# FPGA.net
KiCad netlist of a schematic drawn in Altium Designer
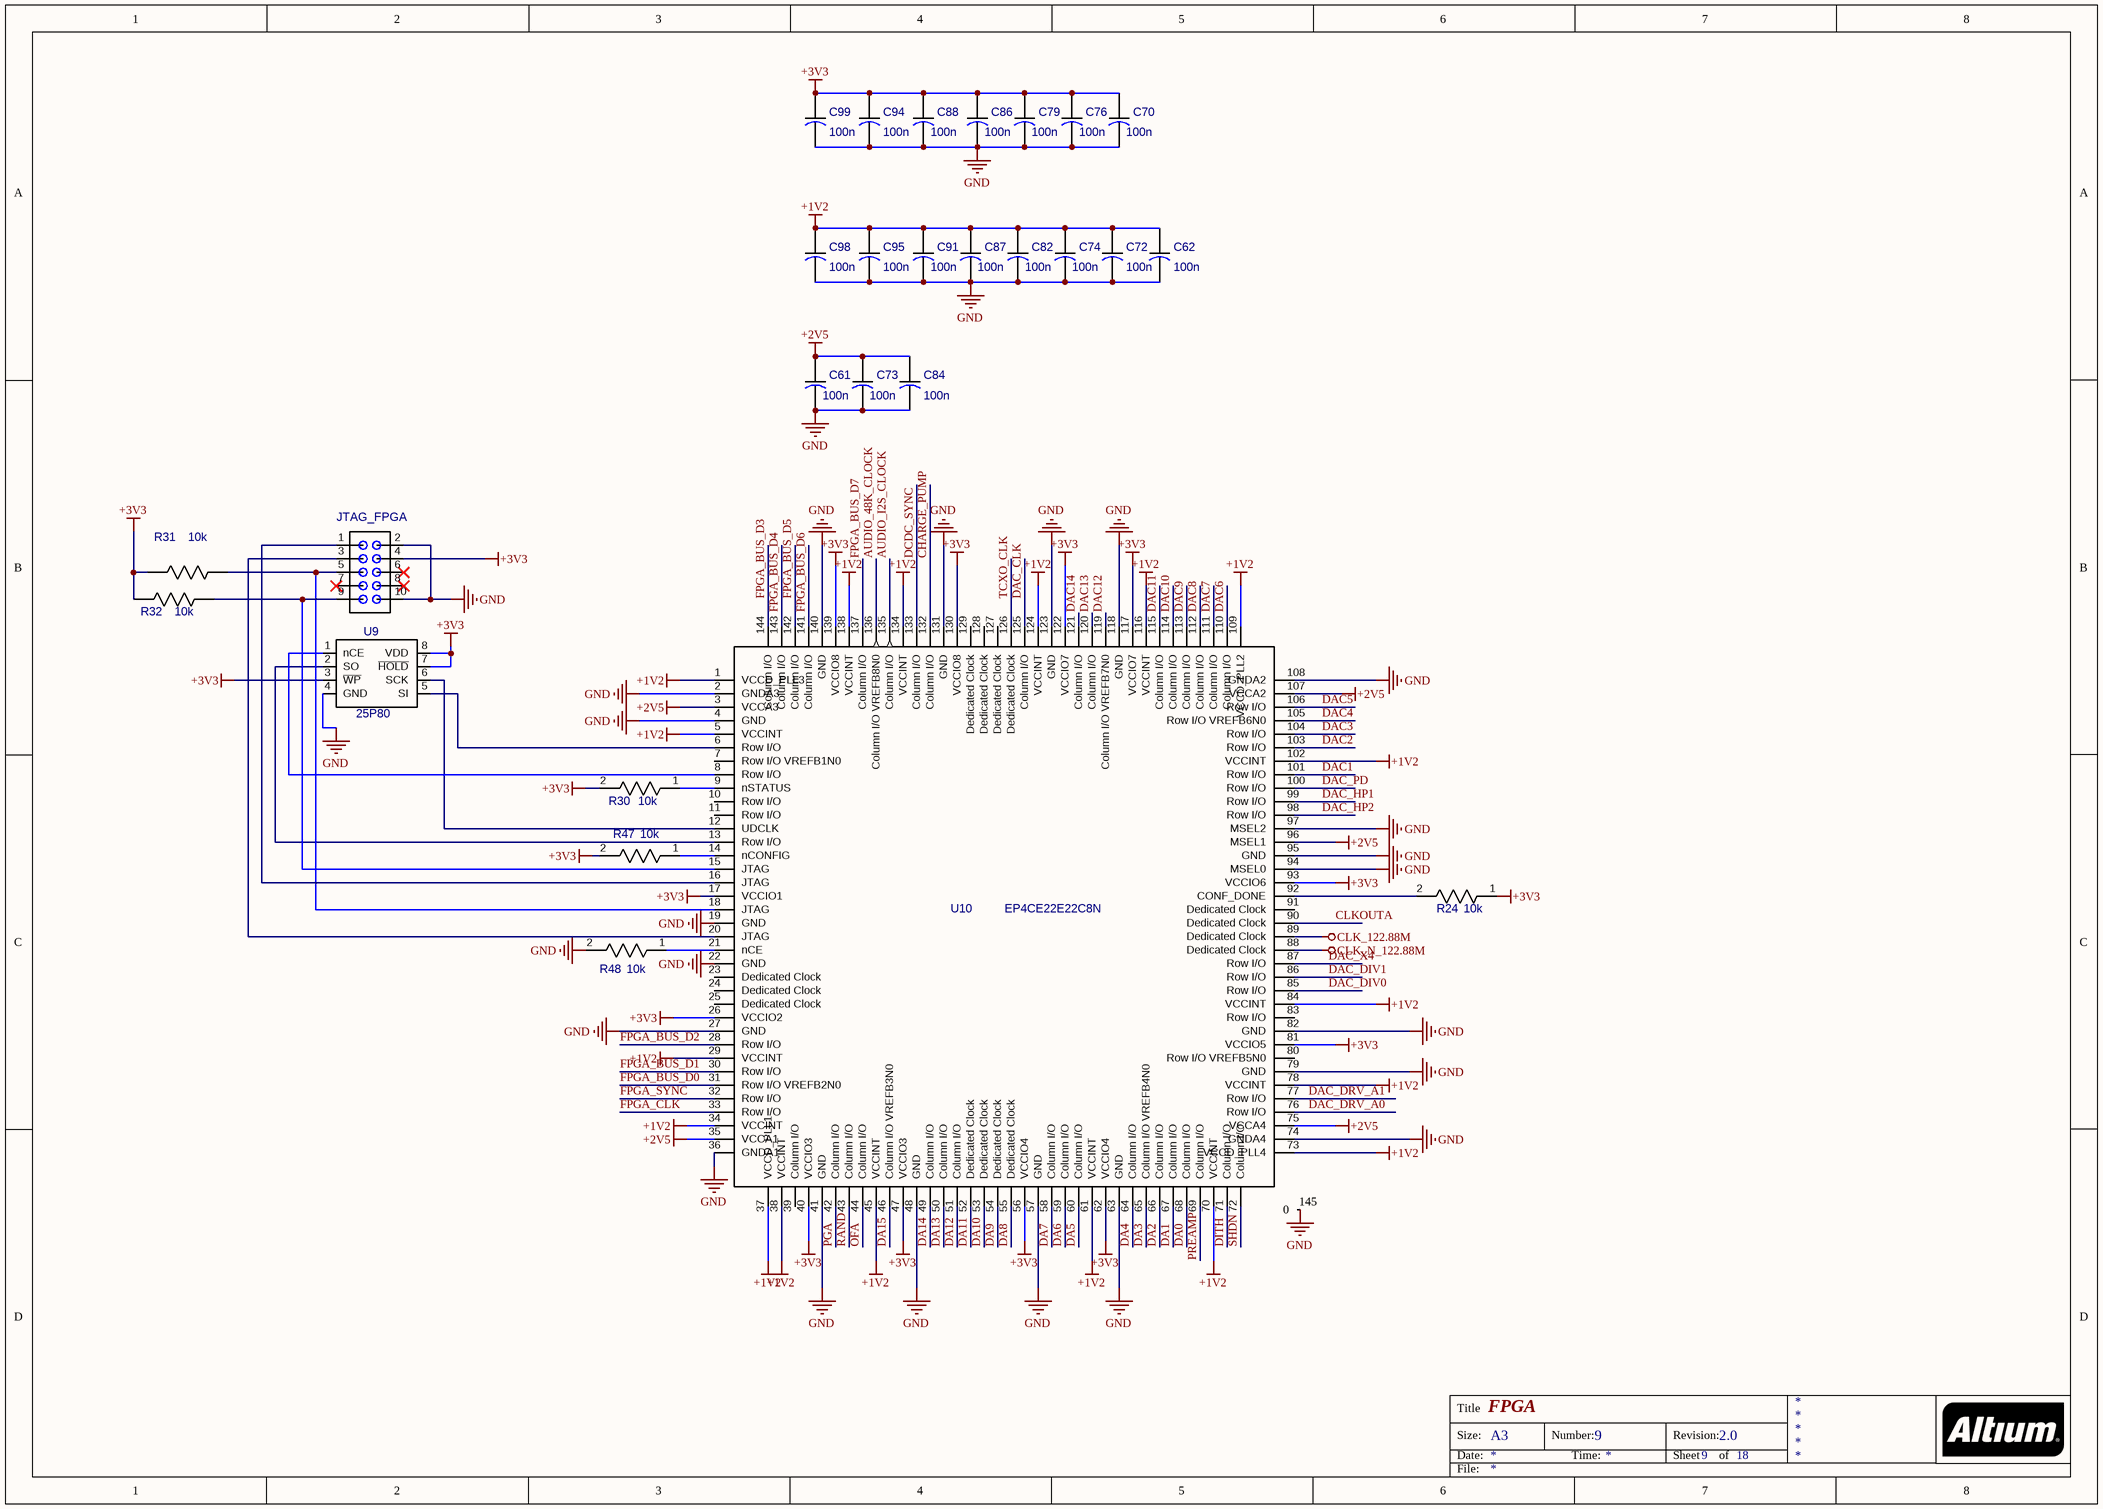
[diagram p0: FPGA.SchDoc]

(export (version "E")
  (design (tool "Eeschema 10.0.6"))
  (components
    (comp (ref "C61")
      (value "100n")
      (footprint "CAP_0805")
      (description "CAP_0805")
      (libsource (lib "*") (part "CAP_0805"))
    )
    (comp (ref "C62")
      (value "100n")
      (footprint "CAP_0805")
      (description "CAP_0805")
      (libsource (lib "*") (part "CAP_0805"))
    )
    (comp (ref "C70")
      (value "100n")
      (footprint "CAP_0805")
      (description "CAP_0805")
      (libsource (lib "*") (part "CAP_0805"))
    )
    (comp (ref "C72")
      (value "100n")
      (footprint "CAP_0805")
      (description "CAP_0805")
      (libsource (lib "*") (part "CAP_0805"))
    )
    (comp (ref "C73")
      (value "100n")
      (footprint "CAP_0805")
      (description "CAP_0805")
      (libsource (lib "*") (part "CAP_0805"))
    )
    (comp (ref "C74")
      (value "100n")
      (footprint "CAP_0805")
      (description "CAP_0805")
      (libsource (lib "*") (part "CAP_0805"))
    )
    (comp (ref "C76")
      (value "100n")
      (footprint "CAP_0805")
      (description "CAP_0805")
      (libsource (lib "*") (part "CAP_0805"))
    )
    (comp (ref "C79")
      (value "100n")
      (footprint "CAP_0805")
      (description "CAP_0805")
      (libsource (lib "*") (part "CAP_0805"))
    )
    (comp (ref "C82")
      (value "100n")
      (footprint "CAP_0805")
      (description "CAP_0805")
      (libsource (lib "*") (part "CAP_0805"))
    )
    (comp (ref "C84")
      (value "100n")
      (footprint "CAP_0805")
      (description "CAP_0805")
      (libsource (lib "*") (part "CAP_0805"))
    )
    (comp (ref "C86")
      (value "100n")
      (footprint "CAP_0805")
      (description "CAP_0805")
      (libsource (lib "*") (part "CAP_0805"))
    )
    (comp (ref "C87")
      (value "100n")
      (footprint "CAP_0805")
      (description "CAP_0805")
      (libsource (lib "*") (part "CAP_0805"))
    )
    (comp (ref "C88")
      (value "100n")
      (footprint "CAP_0805")
      (description "CAP_0805")
      (libsource (lib "*") (part "CAP_0805"))
    )
    (comp (ref "C91")
      (value "100n")
      (footprint "CAP_0805")
      (description "CAP_0805")
      (libsource (lib "*") (part "CAP_0805"))
    )
    (comp (ref "C94")
      (value "100n")
      (footprint "CAP_0805")
      (description "CAP_0805")
      (libsource (lib "*") (part "CAP_0805"))
    )
    (comp (ref "C95")
      (value "100n")
      (footprint "CAP_0805")
      (description "CAP_0805")
      (libsource (lib "*") (part "CAP_0805"))
    )
    (comp (ref "C98")
      (value "100n")
      (footprint "CAP_0805")
      (description "CAP_0805")
      (libsource (lib "*") (part "CAP_0805"))
    )
    (comp (ref "C99")
      (value "100n")
      (footprint "CAP_0805")
      (description "CAP_0805")
      (libsource (lib "*") (part "CAP_0805"))
    )
    (comp (ref "JTAG_FPGA")
      (value "~")
      (footprint "IDC10")
      (description "2*5 Pin")
      (libsource (lib "*") (part "IDC10"))
    )
    (comp (ref "R24")
      (value "10k")
      (footprint "RES_0805")
      (description "RES_0805")
      (libsource (lib "*") (part "RES_0805"))
    )
    (comp (ref "R30")
      (value "10k")
      (footprint "RES_0805")
      (description "RES_0805")
      (libsource (lib "*") (part "RES_0805"))
    )
    (comp (ref "R31")
      (value "10k")
      (footprint "RES_0805")
      (description "RES_0805")
      (libsource (lib "") (part "RES_0805_1"))
    )
    (comp (ref "R32")
      (value "10k")
      (footprint "RES_0805")
      (description "RES_0805")
      (libsource (lib "") (part "RES_0805_1"))
    )
    (comp (ref "R47")
      (value "10k")
      (footprint "RES_0805")
      (description "RES_0805")
      (libsource (lib "*") (part "RES_0805"))
    )
    (comp (ref "R48")
      (value "10k")
      (footprint "RES_0805")
      (description "RES_0805")
      (libsource (lib "*") (part "RES_0805"))
    )
    (comp (ref "U9") (value "25P80") (footprint "25P80") (libsource (lib "*") (part "25P80")))
    (comp (ref "U10")
      (value "EP4CE22E22C8N")
      (footprint "QFP144-20-2222A")
      (libsource (lib "*") (part "EP4CE22E22C8N"))
    )
  )
  (nets
    (net (code "1") (name "+1V2") (class "Default")
      (node (ref "C62") (pin "1") (pinfunction "1_1") (pintype "passive"))
      (node (ref "C72") (pin "1") (pinfunction "1_1") (pintype "passive"))
      (node (ref "C74") (pin "1") (pinfunction "1_1") (pintype "passive"))
      (node (ref "C82") (pin "1") (pinfunction "1_1") (pintype "passive"))
      (node (ref "C87") (pin "1") (pinfunction "1_1") (pintype "passive"))
      (node (ref "C91") (pin "1") (pinfunction "1_1") (pintype "passive"))
      (node (ref "C95") (pin "1") (pinfunction "1_1") (pintype "passive"))
      (node (ref "C98") (pin "1") (pinfunction "1_1") (pintype "passive"))
      (node (ref "U10") (pin "1") (pinfunction "VCCD_PLL3_1") (pintype "passive"))
      (node (ref "U10") (pin "102") (pinfunction "VCCINT_102") (pintype "passive"))
      (node (ref "U10") (pin "109") (pinfunction "VCCD_PLL2_109") (pintype "passive"))
      (node (ref "U10") (pin "116") (pinfunction "VCCINT_116") (pintype "passive"))
      (node (ref "U10") (pin "124") (pinfunction "VCCINT_124") (pintype "passive"))
      (node (ref "U10") (pin "134") (pinfunction "VCCINT_134") (pintype "passive"))
      (node (ref "U10") (pin "138") (pinfunction "VCCINT_138") (pintype "passive"))
      (node (ref "U10") (pin "29") (pinfunction "VCCINT_29") (pintype "passive"))
      (node (ref "U10") (pin "34") (pinfunction "VCCINT_34") (pintype "passive"))
      (node (ref "U10") (pin "37") (pinfunction "VCCD_PLL1_37") (pintype "passive"))
      (node (ref "U10") (pin "38") (pinfunction "VCCINT_38") (pintype "passive"))
      (node (ref "U10") (pin "45") (pinfunction "VCCINT_45") (pintype "passive"))
      (node (ref "U10") (pin "5") (pinfunction "VCCINT_5") (pintype "passive"))
      (node (ref "U10") (pin "61") (pinfunction "VCCINT_61") (pintype "passive"))
      (node (ref "U10") (pin "70") (pinfunction "VCCINT_70") (pintype "passive"))
      (node (ref "U10") (pin "73") (pinfunction "VCCD_PLL4_73") (pintype "passive"))
      (node (ref "U10") (pin "78") (pinfunction "VCCINT_78") (pintype "passive"))
      (node (ref "U10") (pin "84") (pinfunction "VCCINT_84") (pintype "passive"))
    )
    (net (code "2") (name "+2V5") (class "Default")
      (node (ref "C61") (pin "1") (pinfunction "1_1") (pintype "passive"))
      (node (ref "C73") (pin "1") (pinfunction "1_1") (pintype "passive"))
      (node (ref "C84") (pin "1") (pinfunction "1_1") (pintype "passive"))
      (node (ref "U10") (pin "107") (pinfunction "VCCA2_107") (pintype "passive"))
      (node (ref "U10") (pin "3") (pinfunction "VCCA3_3") (pintype "passive"))
      (node (ref "U10") (pin "35") (pinfunction "VCCA1_35") (pintype "passive"))
      (node (ref "U10") (pin "75") (pinfunction "VCCA4_75") (pintype "passive"))
      (node (ref "U10") (pin "96") (pinfunction "MSEL1_96") (pintype "passive"))
    )
    (net (code "3") (name "+3V3") (class "Default")
      (node (ref "C70") (pin "1") (pinfunction "1_1") (pintype "passive"))
      (node (ref "C76") (pin "1") (pinfunction "1_1") (pintype "passive"))
      (node (ref "C79") (pin "1") (pinfunction "1_1") (pintype "passive"))
      (node (ref "C86") (pin "1") (pinfunction "1_1") (pintype "passive"))
      (node (ref "C88") (pin "1") (pinfunction "1_1") (pintype "passive"))
      (node (ref "C94") (pin "1") (pinfunction "1_1") (pintype "passive"))
      (node (ref "C99") (pin "1") (pinfunction "1_1") (pintype "passive"))
      (node (ref "JTAG_FPGA") (pin "4") (pinfunction "4_4") (pintype "passive"))
      (node (ref "R24") (pin "1") (pinfunction "1_1") (pintype "passive"))
      (node (ref "R30") (pin "2") (pinfunction "2_2") (pintype "passive"))
      (node (ref "R31") (pin "2") (pinfunction "2_2") (pintype "passive"))
      (node (ref "R32") (pin "2") (pinfunction "2_2") (pintype "passive"))
      (node (ref "R47") (pin "2") (pinfunction "2_2") (pintype "passive"))
      (node (ref "U10") (pin "117") (pinfunction "VCCIO7_117") (pintype "passive"))
      (node (ref "U10") (pin "122") (pinfunction "VCCIO7_122") (pintype "passive"))
      (node (ref "U10") (pin "130") (pinfunction "VCCIO8_130") (pintype "passive"))
      (node (ref "U10") (pin "139") (pinfunction "VCCIO8_139") (pintype "passive"))
      (node (ref "U10") (pin "17") (pinfunction "VCCIO1_17") (pintype "passive"))
      (node (ref "U10") (pin "26") (pinfunction "VCCIO2_26") (pintype "passive"))
      (node (ref "U10") (pin "40") (pinfunction "VCCIO3_40") (pintype "passive"))
      (node (ref "U10") (pin "47") (pinfunction "VCCIO3_47") (pintype "passive"))
      (node (ref "U10") (pin "56") (pinfunction "VCCIO4_56") (pintype "passive"))
      (node (ref "U10") (pin "62") (pinfunction "VCCIO4_62") (pintype "passive"))
      (node (ref "U10") (pin "81") (pinfunction "VCCIO5_81") (pintype "passive"))
      (node (ref "U10") (pin "93") (pinfunction "VCCIO6_93") (pintype "passive"))
      (node (ref "U9") (pin "3") (pinfunction "~{WP}_3") (pintype "passive"))
      (node (ref "U9") (pin "7") (pinfunction "~{HOLD}_7") (pintype "passive"))
      (node (ref "U9") (pin "8") (pinfunction "VDD_8") (pintype "passive"))
    )
    (net (code "4") (name "/AUDIO_48K_CLOCK") (class "Default")
      (node (ref "U10") (pin "136") (pinfunction "Column_I/O_VREFB8N0_136") (pintype "output"))
    )
    (net (code "5") (name "/AUDIO_I2S_CLOCK") (class "Default")
      (node (ref "U10") (pin "135") (pinfunction "Column_I/O_135") (pintype "output"))
    )
    (net (code "6") (name "/CHARGE_PUMP") (class "Default")
      (node (ref "U10") (pin "132") (pinfunction "Column_I/O_132") (pintype "passive"))
    )
    (net (code "7") (name "/CLKOUTA") (class "Default")
      (node (ref "U10") (pin "90") (pinfunction "Dedicated_Clock_90") (pintype "passive"))
    )
    (net (code "8") (name "/DA0") (class "Default")
      (node (ref "U10") (pin "68") (pinfunction "Column_I/O_68") (pintype "passive"))
    )
    (net (code "9") (name "/DA1") (class "Default")
      (node (ref "U10") (pin "67") (pinfunction "Column_I/O_67") (pintype "passive"))
    )
    (net (code "10") (name "/DA2") (class "Default")
      (node (ref "U10") (pin "66") (pinfunction "Column_I/O_66") (pintype "passive"))
    )
    (net (code "11") (name "/DA3") (class "Default")
      (node (ref "U10") (pin "65") (pinfunction "Column_I/O_VREFB4N0_65") (pintype "passive"))
    )
    (net (code "12") (name "/DA4") (class "Default")
      (node (ref "U10") (pin "64") (pinfunction "Column_I/O_64") (pintype "passive"))
    )
    (net (code "13") (name "/DA5") (class "Default")
      (node (ref "U10") (pin "60") (pinfunction "Column_I/O_60") (pintype "passive"))
    )
    (net (code "14") (name "/DA6") (class "Default")
      (node (ref "U10") (pin "59") (pinfunction "Column_I/O_59") (pintype "passive"))
    )
    (net (code "15") (name "/DA7") (class "Default")
      (node (ref "U10") (pin "58") (pinfunction "Column_I/O_58") (pintype "passive"))
    )
    (net (code "16") (name "/DA8") (class "Default")
      (node (ref "U10") (pin "55") (pinfunction "Dedicated_Clock_55") (pintype "passive"))
    )
    (net (code "17") (name "/DA9") (class "Default")
      (node (ref "U10") (pin "54") (pinfunction "Dedicated_Clock_54") (pintype "passive"))
    )
    (net (code "18") (name "/DA10") (class "Default")
      (node (ref "U10") (pin "53") (pinfunction "Dedicated_Clock_53") (pintype "passive"))
    )
    (net (code "19") (name "/DA11") (class "Default")
      (node (ref "U10") (pin "52") (pinfunction "Dedicated_Clock_52") (pintype "passive"))
    )
    (net (code "20") (name "/DA12") (class "Default")
      (node (ref "U10") (pin "51") (pinfunction "Column_I/O_51") (pintype "passive"))
    )
    (net (code "21") (name "/DA13") (class "Default")
      (node (ref "U10") (pin "50") (pinfunction "Column_I/O_50") (pintype "passive"))
    )
    (net (code "22") (name "/DA14") (class "Default")
      (node (ref "U10") (pin "49") (pinfunction "Column_I/O_49") (pintype "passive"))
    )
    (net (code "23") (name "/DA15") (class "Default")
      (node (ref "U10") (pin "46") (pinfunction "Column_I/O_VREFB3N0_46") (pintype "passive"))
    )
    (net (code "24") (name "/DAC1") (class "Default")
      (node (ref "U10") (pin "101") (pinfunction "Row_I/O_101") (pintype "passive"))
    )
    (net (code "25") (name "/DAC2") (class "Default")
      (node (ref "U10") (pin "103") (pinfunction "Row_I/O_103") (pintype "passive"))
    )
    (net (code "26") (name "/DAC3") (class "Default")
      (node (ref "U10") (pin "104") (pinfunction "Row_I/O_104") (pintype "passive"))
    )
    (net (code "27") (name "/DAC4") (class "Default")
      (node (ref "U10") (pin "105") (pinfunction "Row_I/O_VREFB6N0_105") (pintype "passive"))
    )
    (net (code "28") (name "/DAC5") (class "Default")
      (node (ref "U10") (pin "106") (pinfunction "Row_I/O_106") (pintype "passive"))
    )
    (net (code "29") (name "/DAC6") (class "Default")
      (node (ref "U10") (pin "110") (pinfunction "Column_I/O_110") (pintype "passive"))
    )
    (net (code "30") (name "/DAC7") (class "Default")
      (node (ref "U10") (pin "111") (pinfunction "Column_I/O_111") (pintype "passive"))
    )
    (net (code "31") (name "/DAC8") (class "Default")
      (node (ref "U10") (pin "112") (pinfunction "Column_I/O_112") (pintype "passive"))
    )
    (net (code "32") (name "/DAC9") (class "Default")
      (node (ref "U10") (pin "113") (pinfunction "Column_I/O_113") (pintype "passive"))
    )
    (net (code "33") (name "/DAC10") (class "Default")
      (node (ref "U10") (pin "114") (pinfunction "Column_I/O_114") (pintype "passive"))
    )
    (net (code "34") (name "/DAC11") (class "Default")
      (node (ref "U10") (pin "115") (pinfunction "Column_I/O_115") (pintype "passive"))
    )
    (net (code "35") (name "/DAC12") (class "Default")
      (node (ref "U10") (pin "119") (pinfunction "Column_I/O_VREFB7N0_119") (pintype "passive"))
    )
    (net (code "36") (name "/DAC13") (class "Default")
      (node (ref "U10") (pin "120") (pinfunction "Column_I/O_120") (pintype "passive"))
    )
    (net (code "37") (name "/DAC14") (class "Default")
      (node (ref "U10") (pin "121") (pinfunction "Column_I/O_121") (pintype "passive"))
    )
    (net (code "38") (name "/DAC_CLK") (class "Default")
      (node (ref "U10") (pin "125") (pinfunction "Column_I/O_125") (pintype "passive"))
    )
    (net (code "39") (name "/DAC_DIV0") (class "Default")
      (node (ref "U10") (pin "85") (pinfunction "Row_I/O_85") (pintype "passive"))
    )
    (net (code "40") (name "/DAC_DIV1") (class "Default")
      (node (ref "U10") (pin "86") (pinfunction "Row_I/O_86") (pintype "passive"))
    )
    (net (code "41") (name "/DAC_DRV_A0") (class "Default")
      (node (ref "U10") (pin "76") (pinfunction "Row_I/O_76") (pintype "passive"))
    )
    (net (code "42") (name "/DAC_DRV_A1") (class "Default")
      (node (ref "U10") (pin "77") (pinfunction "Row_I/O_77") (pintype "passive"))
    )
    (net (code "43") (name "/DAC_HP1") (class "Default")
      (node (ref "U10") (pin "99") (pinfunction "Row_I/O_99") (pintype "passive"))
    )
    (net (code "44") (name "/DAC_HP2") (class "Default")
      (node (ref "U10") (pin "98") (pinfunction "Row_I/O_98") (pintype "passive"))
    )
    (net (code "45") (name "/DAC_PD") (class "Default")
      (node (ref "U10") (pin "100") (pinfunction "Row_I/O_100") (pintype "passive"))
    )
    (net (code "46") (name "/DAC_X4") (class "Default")
      (node (ref "U10") (pin "87") (pinfunction "Row_I/O_87") (pintype "passive"))
    )
    (net (code "47") (name "/DCDC_SYNC") (class "Default")
      (node (ref "U10") (pin "133") (pinfunction "Column_I/O_133") (pintype "passive"))
    )
    (net (code "48") (name "/DITH") (class "Default")
      (node (ref "U10") (pin "71") (pinfunction "Column_I/O_71") (pintype "passive"))
    )
    (net (code "49") (name "/FPGA_BUS_D0") (class "Default")
      (node (ref "U10") (pin "31") (pinfunction "Row_I/O_VREFB2N0_31") (pintype "passive"))
    )
    (net (code "50") (name "/FPGA_BUS_D1") (class "Default")
      (node (ref "U10") (pin "30") (pinfunction "Row_I/O_30") (pintype "passive"))
    )
    (net (code "51") (name "/FPGA_BUS_D2") (class "Default")
      (node (ref "U10") (pin "28") (pinfunction "Row_I/O_28") (pintype "passive"))
    )
    (net (code "52") (name "/FPGA_BUS_D3") (class "Default")
      (node (ref "U10") (pin "144") (pinfunction "Column_I/O_144") (pintype "passive"))
    )
    (net (code "53") (name "/FPGA_BUS_D4") (class "Default")
      (node (ref "U10") (pin "143") (pinfunction "Column_I/O_143") (pintype "passive"))
    )
    (net (code "54") (name "/FPGA_BUS_D5") (class "Default")
      (node (ref "U10") (pin "142") (pinfunction "Column_I/O_142") (pintype "passive"))
    )
    (net (code "55") (name "/FPGA_BUS_D6") (class "Default")
      (node (ref "U10") (pin "141") (pinfunction "Column_I/O_141") (pintype "passive"))
    )
    (net (code "56") (name "/FPGA_BUS_D7") (class "Default")
      (node (ref "U10") (pin "137") (pinfunction "Column_I/O_137") (pintype "passive"))
    )
    (net (code "57") (name "/FPGA_CLK") (class "Default")
      (node (ref "U10") (pin "33") (pinfunction "Row_I/O_33") (pintype "passive"))
    )
    (net (code "58") (name "/FPGA_SYNC") (class "Default")
      (node (ref "U10") (pin "32") (pinfunction "Row_I/O_32") (pintype "passive"))
    )
    (net (code "59") (name "/OFA") (class "Default")
      (node (ref "U10") (pin "44") (pinfunction "Column_I/O_44") (pintype "passive"))
    )
    (net (code "60") (name "/PGA") (class "Default")
      (node (ref "U10") (pin "42") (pinfunction "Column_I/O_42") (pintype "passive"))
    )
    (net (code "61") (name "/PREAMP") (class "Default")
      (node (ref "U10") (pin "69") (pinfunction "Column_I/O_69") (pintype "passive"))
    )
    (net (code "62") (name "/RAND") (class "Default")
      (node (ref "U10") (pin "43") (pinfunction "Column_I/O_43") (pintype "passive"))
    )
    (net (code "63") (name "/SHDN") (class "Default")
      (node (ref "U10") (pin "72") (pinfunction "Column_I/O_72") (pintype "passive"))
    )
    (net (code "64") (name "/TCXO_CLK") (class "Default")
      (node (ref "U10") (pin "126") (pinfunction "Dedicated_Clock_126") (pintype "passive"))
    )
    (net (code "65") (name "CLK_122.88M") (class "Default")
      (node (ref "U10") (pin "89") (pinfunction "Dedicated_Clock_89") (pintype "passive"))
    )
    (net (code "66") (name "CLK_N_122.88M") (class "Default")
      (node (ref "U10") (pin "88") (pinfunction "Dedicated_Clock_88") (pintype "passive"))
    )
    (net (code "67") (name "GND") (class "Default")
      (node (ref "C61") (pin "2") (pinfunction "2_2") (pintype "passive"))
      (node (ref "C62") (pin "2") (pinfunction "2_2") (pintype "passive"))
      (node (ref "C70") (pin "2") (pinfunction "2_2") (pintype "passive"))
      (node (ref "C72") (pin "2") (pinfunction "2_2") (pintype "passive"))
      (node (ref "C73") (pin "2") (pinfunction "2_2") (pintype "passive"))
      (node (ref "C74") (pin "2") (pinfunction "2_2") (pintype "passive"))
      (node (ref "C76") (pin "2") (pinfunction "2_2") (pintype "passive"))
      (node (ref "C79") (pin "2") (pinfunction "2_2") (pintype "passive"))
      (node (ref "C82") (pin "2") (pinfunction "2_2") (pintype "passive"))
      (node (ref "C84") (pin "2") (pinfunction "2_2") (pintype "passive"))
      (node (ref "C86") (pin "2") (pinfunction "2_2") (pintype "passive"))
      (node (ref "C87") (pin "2") (pinfunction "2_2") (pintype "passive"))
      (node (ref "C88") (pin "2") (pinfunction "2_2") (pintype "passive"))
      (node (ref "C91") (pin "2") (pinfunction "2_2") (pintype "passive"))
      (node (ref "C94") (pin "2") (pinfunction "2_2") (pintype "passive"))
      (node (ref "C95") (pin "2") (pinfunction "2_2") (pintype "passive"))
      (node (ref "C98") (pin "2") (pinfunction "2_2") (pintype "passive"))
      (node (ref "C99") (pin "2") (pinfunction "2_2") (pintype "passive"))
      (node (ref "JTAG_FPGA") (pin "10") (pinfunction "10_10") (pintype "passive"))
      (node (ref "JTAG_FPGA") (pin "2") (pinfunction "2_2") (pintype "passive"))
      (node (ref "R48") (pin "2") (pinfunction "2_2") (pintype "passive"))
      (node (ref "U10") (pin "108") (pinfunction "GNDA2_108") (pintype "passive"))
      (node (ref "U10") (pin "118") (pinfunction "GND_118") (pintype "passive"))
      (node (ref "U10") (pin "123") (pinfunction "GND_123") (pintype "passive"))
      (node (ref "U10") (pin "131") (pinfunction "GND_131") (pintype "passive"))
      (node (ref "U10") (pin "140") (pinfunction "GND_140") (pintype "passive"))
      (node (ref "U10") (pin "145") (pinfunction "0_145") (pintype "passive"))
      (node (ref "U10") (pin "19") (pinfunction "GND_19") (pintype "passive"))
      (node (ref "U10") (pin "2") (pinfunction "GNDA3_2") (pintype "passive"))
      (node (ref "U10") (pin "22") (pinfunction "GND_22") (pintype "passive"))
      (node (ref "U10") (pin "27") (pinfunction "GND_27") (pintype "passive"))
      (node (ref "U10") (pin "36") (pinfunction "GNDA1_36") (pintype "passive"))
      (node (ref "U10") (pin "4") (pinfunction "GND_4") (pintype "passive"))
      (node (ref "U10") (pin "41") (pinfunction "GND_41") (pintype "passive"))
      (node (ref "U10") (pin "48") (pinfunction "GND_48") (pintype "passive"))
      (node (ref "U10") (pin "57") (pinfunction "GND_57") (pintype "passive"))
      (node (ref "U10") (pin "63") (pinfunction "GND_63") (pintype "passive"))
      (node (ref "U10") (pin "74") (pinfunction "GNDA4_74") (pintype "passive"))
      (node (ref "U10") (pin "79") (pinfunction "GND_79") (pintype "passive"))
      (node (ref "U10") (pin "82") (pinfunction "GND_82") (pintype "passive"))
      (node (ref "U10") (pin "94") (pinfunction "MSEL0_94") (pintype "passive"))
      (node (ref "U10") (pin "95") (pinfunction "GND_95") (pintype "passive"))
      (node (ref "U10") (pin "97") (pinfunction "MSEL2_97") (pintype "passive"))
      (node (ref "U9") (pin "4") (pinfunction "GND_4") (pintype "passive"))
    )
    (net (code "68") (name "Net-(JTAG_FPGA-Pad1)") (class "Default")
      (node (ref "JTAG_FPGA") (pin "1") (pinfunction "1_1") (pintype "passive"))
      (node (ref "U10") (pin "16") (pinfunction "JTAG_16") (pintype "passive"))
    )
    (net (code "69") (name "Net-(JTAG_FPGA-Pad3)") (class "Default")
      (node (ref "JTAG_FPGA") (pin "3") (pinfunction "3_3") (pintype "passive"))
      (node (ref "U10") (pin "20") (pinfunction "JTAG_20") (pintype "passive"))
    )
    (net (code "70") (name "Net-(JTAG_FPGA-Pad5)") (class "Default")
      (node (ref "JTAG_FPGA") (pin "5") (pinfunction "5_5") (pintype "passive"))
      (node (ref "R31") (pin "1") (pinfunction "1_1") (pintype "passive"))
      (node (ref "U10") (pin "18") (pinfunction "JTAG_18") (pintype "passive"))
    )
    (net (code "71") (name "Net-(JTAG_FPGA-Pad9)") (class "Default")
      (node (ref "JTAG_FPGA") (pin "9") (pinfunction "9_9") (pintype "passive"))
      (node (ref "R32") (pin "1") (pinfunction "1_1") (pintype "passive"))
      (node (ref "U10") (pin "15") (pinfunction "JTAG_15") (pintype "passive"))
    )
    (net (code "72") (name "Net-(U9-SI)") (class "Default")
      (node (ref "U10") (pin "6") (pinfunction "Row_I/O_6") (pintype "passive"))
      (node (ref "U9") (pin "5") (pinfunction "SI_5") (pintype "passive"))
    )
    (net (code "73") (name "Net-(U9-SO)") (class "Default")
      (node (ref "U10") (pin "13") (pinfunction "Row_I/O_13") (pintype "passive"))
      (node (ref "U9") (pin "2") (pinfunction "SO_2") (pintype "passive"))
    )
    (net (code "74") (name "Net-(U9-nCE)") (class "Default")
      (node (ref "U10") (pin "8") (pinfunction "Row_I/O_8") (pintype "passive"))
      (node (ref "U9") (pin "1") (pinfunction "nCE_1") (pintype "passive"))
    )
    (net (code "75") (name "Net-(U10-CONF_DONE)") (class "Default")
      (node (ref "R24") (pin "2") (pinfunction "2_2") (pintype "passive"))
      (node (ref "U10") (pin "92") (pinfunction "CONF_DONE_92") (pintype "passive"))
    )
    (net (code "76") (name "Net-(U10-UDCLK)") (class "Default")
      (node (ref "U10") (pin "12") (pinfunction "UDCLK_12") (pintype "passive"))
      (node (ref "U9") (pin "6") (pinfunction "SCK_6") (pintype "passive"))
    )
    (net (code "77") (name "Net-(U10-nCE)") (class "Default")
      (node (ref "R48") (pin "1") (pinfunction "1_1") (pintype "passive"))
      (node (ref "U10") (pin "21") (pinfunction "nCE_21") (pintype "passive"))
    )
    (net (code "78") (name "Net-(U10-nCONFIG)") (class "Default")
      (node (ref "R47") (pin "1") (pinfunction "1_1") (pintype "passive"))
      (node (ref "U10") (pin "14") (pinfunction "nCONFIG_14") (pintype "passive"))
    )
    (net (code "79") (name "Net-(U10-nSTATUS)") (class "Default")
      (node (ref "R30") (pin "1") (pinfunction "1_1") (pintype "passive"))
      (node (ref "U10") (pin "9") (pinfunction "nSTATUS_9") (pintype "passive"))
    )
    (net (code "80") (name "unconnected-(JTAG_FPGA-Pad6)") (class "Default")
      (node (ref "JTAG_FPGA") (pin "6") (pinfunction "6_6") (pintype "passive+no_connect"))
    )
    (net (code "81") (name "unconnected-(JTAG_FPGA-Pad7)") (class "Default")
      (node (ref "JTAG_FPGA") (pin "7") (pinfunction "7_7") (pintype "passive+no_connect"))
    )
    (net (code "82") (name "unconnected-(JTAG_FPGA-Pad8)") (class "Default")
      (node (ref "JTAG_FPGA") (pin "8") (pinfunction "8_8") (pintype "passive+no_connect"))
    )
    (net (code "83") (name "unconnected-(U10-Column_I{slash}O-Pad39)") (class "Default")
      (node (ref "U10") (pin "39") (pinfunction "Column_I/O_39") (pintype "passive"))
    )
    (net (code "84") (name "unconnected-(U10-Dedicated_Clock-Pad23)") (class "Default")
      (node (ref "U10") (pin "23") (pinfunction "Dedicated_Clock_23") (pintype "passive"))
    )
    (net (code "85") (name "unconnected-(U10-Dedicated_Clock-Pad24)") (class "Default")
      (node (ref "U10") (pin "24") (pinfunction "Dedicated_Clock_24") (pintype "passive"))
    )
    (net (code "86") (name "unconnected-(U10-Dedicated_Clock-Pad25)") (class "Default")
      (node (ref "U10") (pin "25") (pinfunction "Dedicated_Clock_25") (pintype "passive"))
    )
    (net (code "87") (name "unconnected-(U10-Dedicated_Clock-Pad91)") (class "Default")
      (node (ref "U10") (pin "91") (pinfunction "Dedicated_Clock_91") (pintype "passive"))
    )
    (net (code "88") (name "unconnected-(U10-Dedicated_Clock-Pad127)") (class "Default")
      (node (ref "U10") (pin "127") (pinfunction "Dedicated_Clock_127") (pintype "passive"))
    )
    (net (code "89") (name "unconnected-(U10-Dedicated_Clock-Pad128)") (class "Default")
      (node (ref "U10") (pin "128") (pinfunction "Dedicated_Clock_128") (pintype "passive"))
    )
    (net (code "90") (name "unconnected-(U10-Dedicated_Clock-Pad129)") (class "Default")
      (node (ref "U10") (pin "129") (pinfunction "Dedicated_Clock_129") (pintype "passive"))
    )
    (net (code "91") (name "unconnected-(U10-Row_I{slash}O-Pad10)") (class "Default")
      (node (ref "U10") (pin "10") (pinfunction "Row_I/O_10") (pintype "passive"))
    )
    (net (code "92") (name "unconnected-(U10-Row_I{slash}O-Pad11)") (class "Default")
      (node (ref "U10") (pin "11") (pinfunction "Row_I/O_11") (pintype "passive"))
    )
    (net (code "93") (name "unconnected-(U10-Row_I{slash}O-Pad83)") (class "Default")
      (node (ref "U10") (pin "83") (pinfunction "Row_I/O_83") (pintype "passive"))
    )
    (net (code "94") (name "unconnected-(U10-Row_I{slash}O_VREFB1N0-Pad7)") (class "Default")
      (node (ref "U10") (pin "7") (pinfunction "Row_I/O_VREFB1N0_7") (pintype "passive"))
    )
    (net (code "95") (name "unconnected-(U10-Row_I{slash}O_VREFB5N0-Pad80)") (class "Default")
      (node (ref "U10") (pin "80") (pinfunction "Row_I/O_VREFB5N0_80") (pintype "passive"))
    )
  )
)
